# EXT_SCR.net
KiCad netlist of a schematic drawn in EAGLE
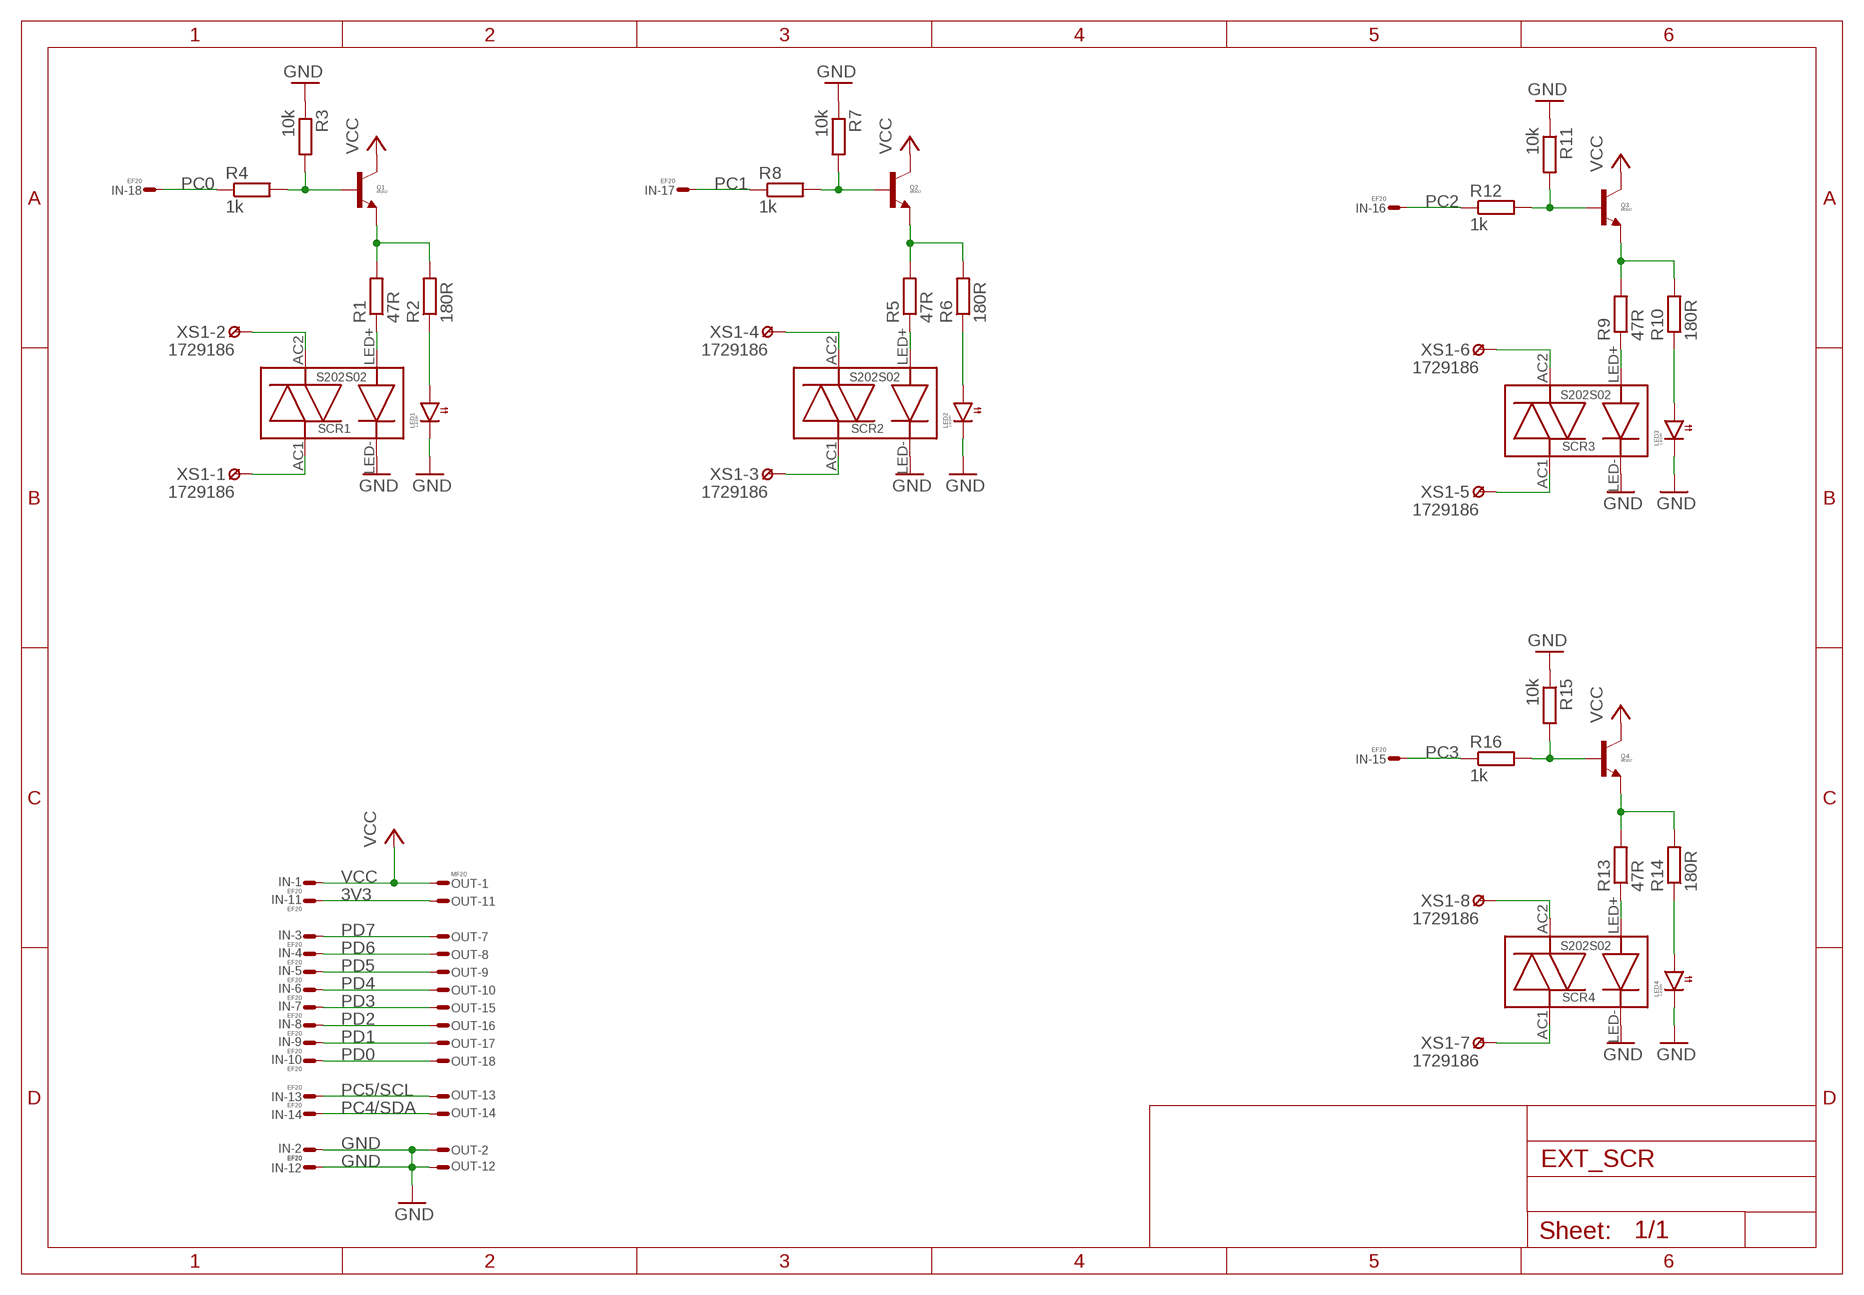
[diagram p0: schematic, sheet 1]

(export (version "E")
  (design (tool "Eeschema 10.0.6"))
  (components
    (comp (ref "IN")
      (value "EF20")
      (footprint "eagle-import:FE10-2WSS")
      (libsource (lib "eagle-import") (part "FE20ELSS"))
    )
    (comp (ref "LED1")
      (value "LEDR")
      (footprint "eagle-import:1206")
      (libsource (lib "eagle-import") (part "LED1206"))
    )
    (comp (ref "LED2")
      (value "LEDR")
      (footprint "eagle-import:1206")
      (libsource (lib "eagle-import") (part "LED1206"))
    )
    (comp (ref "LED3")
      (value "LEDR")
      (footprint "eagle-import:1206")
      (libsource (lib "eagle-import") (part "LED1206"))
    )
    (comp (ref "LED4")
      (value "LEDR")
      (footprint "eagle-import:1206")
      (libsource (lib "eagle-import") (part "LED1206"))
    )
    (comp (ref "OUT")
      (value "MF20")
      (footprint "eagle-import:ML20LS")
      (libsource (lib "eagle-import") (part "ML20?ELS"))
    )
    (comp (ref "Q1")
      (value "BC817")
      (footprint "eagle-import:SOT23")
      (libsource (lib "eagle-import") (part "NPN23"))
    )
    (comp (ref "Q2")
      (value "BC817")
      (footprint "eagle-import:SOT23")
      (libsource (lib "eagle-import") (part "NPN23"))
    )
    (comp (ref "Q3")
      (value "BC817")
      (footprint "eagle-import:SOT23")
      (libsource (lib "eagle-import") (part "NPN23"))
    )
    (comp (ref "Q4")
      (value "BC817")
      (footprint "eagle-import:SOT23")
      (libsource (lib "eagle-import") (part "NPN23"))
    )
    (comp (ref "R1")
      (value "47R")
      (footprint "eagle-import:0603")
      (libsource (lib "eagle-import") (part "R0603"))
    )
    (comp (ref "R2")
      (value "180R")
      (footprint "eagle-import:0603")
      (libsource (lib "eagle-import") (part "R0603"))
    )
    (comp (ref "R3")
      (value "10k")
      (footprint "eagle-import:0603")
      (libsource (lib "eagle-import") (part "R0603"))
    )
    (comp (ref "R4")
      (value "1k")
      (footprint "eagle-import:0603")
      (libsource (lib "eagle-import") (part "R0603"))
    )
    (comp (ref "R5")
      (value "47R")
      (footprint "eagle-import:0603")
      (libsource (lib "eagle-import") (part "R0603"))
    )
    (comp (ref "R6")
      (value "180R")
      (footprint "eagle-import:0603")
      (libsource (lib "eagle-import") (part "R0603"))
    )
    (comp (ref "R7")
      (value "10k")
      (footprint "eagle-import:0603")
      (libsource (lib "eagle-import") (part "R0603"))
    )
    (comp (ref "R8")
      (value "1k")
      (footprint "eagle-import:0603")
      (libsource (lib "eagle-import") (part "R0603"))
    )
    (comp (ref "R9")
      (value "47R")
      (footprint "eagle-import:0603")
      (libsource (lib "eagle-import") (part "R0603"))
    )
    (comp (ref "R10")
      (value "180R")
      (footprint "eagle-import:0603")
      (libsource (lib "eagle-import") (part "R0603"))
    )
    (comp (ref "R11")
      (value "10k")
      (footprint "eagle-import:0603")
      (libsource (lib "eagle-import") (part "R0603"))
    )
    (comp (ref "R12")
      (value "1k")
      (footprint "eagle-import:0603")
      (libsource (lib "eagle-import") (part "R0603"))
    )
    (comp (ref "R13")
      (value "47R")
      (footprint "eagle-import:0603")
      (libsource (lib "eagle-import") (part "R0603"))
    )
    (comp (ref "R14")
      (value "180R")
      (footprint "eagle-import:0603")
      (libsource (lib "eagle-import") (part "R0603"))
    )
    (comp (ref "R15")
      (value "10k")
      (footprint "eagle-import:0603")
      (libsource (lib "eagle-import") (part "R0603"))
    )
    (comp (ref "R16")
      (value "1k")
      (footprint "eagle-import:0603")
      (libsource (lib "eagle-import") (part "R0603"))
    )
    (comp (ref "SCR1")
      (value "S202S02")
      (footprint "eagle-import:S202")
      (libsource (lib "eagle-import") (part "S202"))
    )
    (comp (ref "SCR2")
      (value "S202S02")
      (footprint "eagle-import:S202")
      (libsource (lib "eagle-import") (part "S202"))
    )
    (comp (ref "SCR3")
      (value "S202S02")
      (footprint "eagle-import:S202")
      (libsource (lib "eagle-import") (part "S202"))
    )
    (comp (ref "SCR4")
      (value "S202S02")
      (footprint "eagle-import:S202")
      (libsource (lib "eagle-import") (part "S202"))
    )
    (comp (ref "XS1")
      (value "1729186")
      (footprint "eagle-import:W237-8P")
      (libsource (lib "eagle-import") (part "CON8-SS508"))
    )
  )
  (nets
    (net (code "1") (name "/3V3") (class "Default")
      (node (ref "IN") (pin "P$11") (pinfunction "S_P$11") (pintype "passive"))
      (node (ref "OUT") (pin "P$11") (pinfunction "S_P$11") (pintype "passive"))
    )
    (net (code "2") (name "/PC0") (class "Default")
      (node (ref "IN") (pin "P$18") (pinfunction "S_P$18") (pintype "passive"))
      (node (ref "R4") (pin "1") (pinfunction "1_1") (pintype "passive"))
    )
    (net (code "3") (name "/PC1") (class "Default")
      (node (ref "IN") (pin "P$17") (pinfunction "S_P$17") (pintype "passive"))
      (node (ref "R8") (pin "1") (pinfunction "1_1") (pintype "passive"))
    )
    (net (code "4") (name "/PC2") (class "Default")
      (node (ref "IN") (pin "P$16") (pinfunction "S_P$16") (pintype "passive"))
      (node (ref "R12") (pin "1") (pinfunction "1_1") (pintype "passive"))
    )
    (net (code "5") (name "/PC3") (class "Default")
      (node (ref "IN") (pin "P$15") (pinfunction "S_P$15") (pintype "passive"))
      (node (ref "R16") (pin "1") (pinfunction "1_1") (pintype "passive"))
    )
    (net (code "6") (name "/PC4{slash}SDA") (class "Default")
      (node (ref "IN") (pin "P$14") (pinfunction "S_P$14") (pintype "passive"))
      (node (ref "OUT") (pin "P$14") (pinfunction "S_P$14") (pintype "passive"))
    )
    (net (code "7") (name "/PC5{slash}SCL") (class "Default")
      (node (ref "IN") (pin "P$13") (pinfunction "S_P$13") (pintype "passive"))
      (node (ref "OUT") (pin "P$13") (pinfunction "S_P$13") (pintype "passive"))
    )
    (net (code "8") (name "/PD0") (class "Default")
      (node (ref "IN") (pin "P$10") (pinfunction "S_P$10") (pintype "passive"))
      (node (ref "OUT") (pin "P$18") (pinfunction "S_P$18") (pintype "passive"))
    )
    (net (code "9") (name "/PD1") (class "Default")
      (node (ref "IN") (pin "P$9") (pinfunction "S_P$9") (pintype "passive"))
      (node (ref "OUT") (pin "P$17") (pinfunction "S_P$17") (pintype "passive"))
    )
    (net (code "10") (name "/PD2") (class "Default")
      (node (ref "IN") (pin "P$8") (pinfunction "S_P$8") (pintype "passive"))
      (node (ref "OUT") (pin "P$16") (pinfunction "S_P$16") (pintype "passive"))
    )
    (net (code "11") (name "/PD3") (class "Default")
      (node (ref "IN") (pin "P$7") (pinfunction "S_P$7") (pintype "passive"))
      (node (ref "OUT") (pin "P$15") (pinfunction "S_P$15") (pintype "passive"))
    )
    (net (code "12") (name "/PD4") (class "Default")
      (node (ref "IN") (pin "P$6") (pinfunction "S_P$6") (pintype "passive"))
      (node (ref "OUT") (pin "P$10") (pinfunction "S_P$10") (pintype "passive"))
    )
    (net (code "13") (name "/PD5") (class "Default")
      (node (ref "IN") (pin "P$5") (pinfunction "S_P$5") (pintype "passive"))
      (node (ref "OUT") (pin "P$9") (pinfunction "S_P$9") (pintype "passive"))
    )
    (net (code "14") (name "/PD6") (class "Default")
      (node (ref "IN") (pin "P$4") (pinfunction "S_P$4") (pintype "passive"))
      (node (ref "OUT") (pin "P$8") (pinfunction "S_P$8") (pintype "passive"))
    )
    (net (code "15") (name "/PD7") (class "Default")
      (node (ref "IN") (pin "P$3") (pinfunction "S_P$3") (pintype "passive"))
      (node (ref "OUT") (pin "P$7") (pinfunction "S_P$7") (pintype "passive"))
    )
    (net (code "16") (name "GND") (class "Default")
      (node (ref "IN") (pin "P$12") (pinfunction "S_P$12") (pintype "passive"))
      (node (ref "IN") (pin "P$2") (pinfunction "S_P$2") (pintype "passive"))
      (node (ref "LED1") (pin "2") (pinfunction "C_2") (pintype "bidirectional"))
      (node (ref "LED2") (pin "2") (pinfunction "C_2") (pintype "bidirectional"))
      (node (ref "LED3") (pin "2") (pinfunction "C_2") (pintype "bidirectional"))
      (node (ref "LED4") (pin "2") (pinfunction "C_2") (pintype "bidirectional"))
      (node (ref "OUT") (pin "P$12") (pinfunction "S_P$12") (pintype "passive"))
      (node (ref "OUT") (pin "P$2") (pinfunction "S_P$2") (pintype "passive"))
      (node (ref "R11") (pin "1") (pinfunction "1_1") (pintype "passive"))
      (node (ref "R15") (pin "1") (pinfunction "1_1") (pintype "passive"))
      (node (ref "R3") (pin "1") (pinfunction "1_1") (pintype "passive"))
      (node (ref "R7") (pin "1") (pinfunction "1_1") (pintype "passive"))
      (node (ref "SCR1") (pin "LED-") (pinfunction "L-_LED-") (pintype "bidirectional"))
      (node (ref "SCR2") (pin "LED-") (pinfunction "L-_LED-") (pintype "bidirectional"))
      (node (ref "SCR3") (pin "LED-") (pinfunction "L-_LED-") (pintype "bidirectional"))
      (node (ref "SCR4") (pin "LED-") (pinfunction "L-_LED-") (pintype "bidirectional"))
    )
    (net (code "17") (name "Net-(LED1-A)") (class "Default")
      (node (ref "LED1") (pin "1") (pinfunction "A_1") (pintype "bidirectional"))
      (node (ref "R2") (pin "1") (pinfunction "1_1") (pintype "passive"))
    )
    (net (code "18") (name "Net-(LED2-A)") (class "Default")
      (node (ref "LED2") (pin "1") (pinfunction "A_1") (pintype "bidirectional"))
      (node (ref "R6") (pin "1") (pinfunction "1_1") (pintype "passive"))
    )
    (net (code "19") (name "Net-(LED3-A)") (class "Default")
      (node (ref "LED3") (pin "1") (pinfunction "A_1") (pintype "bidirectional"))
      (node (ref "R10") (pin "1") (pinfunction "1_1") (pintype "passive"))
    )
    (net (code "20") (name "Net-(LED4-A)") (class "Default")
      (node (ref "LED4") (pin "1") (pinfunction "A_1") (pintype "bidirectional"))
      (node (ref "R14") (pin "1") (pinfunction "1_1") (pintype "passive"))
    )
    (net (code "21") (name "Net-(Q1-B)") (class "Default")
      (node (ref "Q1") (pin "1") (pinfunction "B_1") (pintype "passive"))
      (node (ref "R3") (pin "2") (pinfunction "2_2") (pintype "passive"))
      (node (ref "R4") (pin "2") (pinfunction "2_2") (pintype "passive"))
    )
    (net (code "22") (name "Net-(Q1-E)") (class "Default")
      (node (ref "Q1") (pin "2") (pinfunction "E_2") (pintype "passive"))
      (node (ref "R1") (pin "2") (pinfunction "2_2") (pintype "passive"))
      (node (ref "R2") (pin "2") (pinfunction "2_2") (pintype "passive"))
    )
    (net (code "23") (name "Net-(Q2-B)") (class "Default")
      (node (ref "Q2") (pin "1") (pinfunction "B_1") (pintype "passive"))
      (node (ref "R7") (pin "2") (pinfunction "2_2") (pintype "passive"))
      (node (ref "R8") (pin "2") (pinfunction "2_2") (pintype "passive"))
    )
    (net (code "24") (name "Net-(Q2-E)") (class "Default")
      (node (ref "Q2") (pin "2") (pinfunction "E_2") (pintype "passive"))
      (node (ref "R5") (pin "2") (pinfunction "2_2") (pintype "passive"))
      (node (ref "R6") (pin "2") (pinfunction "2_2") (pintype "passive"))
    )
    (net (code "25") (name "Net-(Q3-B)") (class "Default")
      (node (ref "Q3") (pin "1") (pinfunction "B_1") (pintype "passive"))
      (node (ref "R11") (pin "2") (pinfunction "2_2") (pintype "passive"))
      (node (ref "R12") (pin "2") (pinfunction "2_2") (pintype "passive"))
    )
    (net (code "26") (name "Net-(Q3-E)") (class "Default")
      (node (ref "Q3") (pin "2") (pinfunction "E_2") (pintype "passive"))
      (node (ref "R10") (pin "2") (pinfunction "2_2") (pintype "passive"))
      (node (ref "R9") (pin "2") (pinfunction "2_2") (pintype "passive"))
    )
    (net (code "27") (name "Net-(Q4-B)") (class "Default")
      (node (ref "Q4") (pin "1") (pinfunction "B_1") (pintype "passive"))
      (node (ref "R15") (pin "2") (pinfunction "2_2") (pintype "passive"))
      (node (ref "R16") (pin "2") (pinfunction "2_2") (pintype "passive"))
    )
    (net (code "28") (name "Net-(Q4-E)") (class "Default")
      (node (ref "Q4") (pin "2") (pinfunction "E_2") (pintype "passive"))
      (node (ref "R13") (pin "2") (pinfunction "2_2") (pintype "passive"))
      (node (ref "R14") (pin "2") (pinfunction "2_2") (pintype "passive"))
    )
    (net (code "29") (name "Net-(SCR1-L+)") (class "Default")
      (node (ref "R1") (pin "1") (pinfunction "1_1") (pintype "passive"))
      (node (ref "SCR1") (pin "LED+") (pinfunction "L+_LED+") (pintype "bidirectional"))
    )
    (net (code "30") (name "Net-(SCR2-L+)") (class "Default")
      (node (ref "R5") (pin "1") (pinfunction "1_1") (pintype "passive"))
      (node (ref "SCR2") (pin "LED+") (pinfunction "L+_LED+") (pintype "bidirectional"))
    )
    (net (code "31") (name "Net-(SCR3-L+)") (class "Default")
      (node (ref "R9") (pin "1") (pinfunction "1_1") (pintype "passive"))
      (node (ref "SCR3") (pin "LED+") (pinfunction "L+_LED+") (pintype "bidirectional"))
    )
    (net (code "32") (name "Net-(SCR4-L+)") (class "Default")
      (node (ref "R13") (pin "1") (pinfunction "1_1") (pintype "passive"))
      (node (ref "SCR4") (pin "LED+") (pinfunction "L+_LED+") (pintype "bidirectional"))
    )
    (net (code "33") (name "Net-(XS1A-K)") (class "Default")
      (node (ref "SCR1") (pin "AC1") (pinfunction "AC1_AC1") (pintype "bidirectional"))
      (node (ref "XS1") (pin "1") (pinfunction "K_1") (pintype "passive"))
    )
    (net (code "34") (name "Net-(XS1B-K)") (class "Default")
      (node (ref "SCR1") (pin "AC2") (pinfunction "AC2_AC2") (pintype "bidirectional"))
      (node (ref "XS1") (pin "2") (pinfunction "K_2") (pintype "passive"))
    )
    (net (code "35") (name "Net-(XS1C-K)") (class "Default")
      (node (ref "SCR2") (pin "AC1") (pinfunction "AC1_AC1") (pintype "bidirectional"))
      (node (ref "XS1") (pin "3") (pinfunction "K_3") (pintype "passive"))
    )
    (net (code "36") (name "Net-(XS1D-K)") (class "Default")
      (node (ref "SCR2") (pin "AC2") (pinfunction "AC2_AC2") (pintype "bidirectional"))
      (node (ref "XS1") (pin "4") (pinfunction "K_4") (pintype "passive"))
    )
    (net (code "37") (name "Net-(XS1E-K)") (class "Default")
      (node (ref "SCR3") (pin "AC1") (pinfunction "AC1_AC1") (pintype "bidirectional"))
      (node (ref "XS1") (pin "5") (pinfunction "K_5") (pintype "passive"))
    )
    (net (code "38") (name "Net-(XS1F-K)") (class "Default")
      (node (ref "SCR3") (pin "AC2") (pinfunction "AC2_AC2") (pintype "bidirectional"))
      (node (ref "XS1") (pin "6") (pinfunction "K_6") (pintype "passive"))
    )
    (net (code "39") (name "Net-(XS1G-K)") (class "Default")
      (node (ref "SCR4") (pin "AC1") (pinfunction "AC1_AC1") (pintype "bidirectional"))
      (node (ref "XS1") (pin "7") (pinfunction "K_7") (pintype "passive"))
    )
    (net (code "40") (name "Net-(XS1H-K)") (class "Default")
      (node (ref "SCR4") (pin "AC2") (pinfunction "AC2_AC2") (pintype "bidirectional"))
      (node (ref "XS1") (pin "8") (pinfunction "K_8") (pintype "passive"))
    )
    (net (code "41") (name "VCC") (class "Default")
      (node (ref "IN") (pin "P$1") (pinfunction "S_P$1") (pintype "passive"))
      (node (ref "OUT") (pin "P$1") (pinfunction "S_P$1") (pintype "passive"))
      (node (ref "Q1") (pin "3") (pinfunction "C_3") (pintype "passive"))
      (node (ref "Q2") (pin "3") (pinfunction "C_3") (pintype "passive"))
      (node (ref "Q3") (pin "3") (pinfunction "C_3") (pintype "passive"))
      (node (ref "Q4") (pin "3") (pinfunction "C_3") (pintype "passive"))
    )
  )
)
